# BackPage.net
KiCad netlist of a schematic drawn in Altium Designer
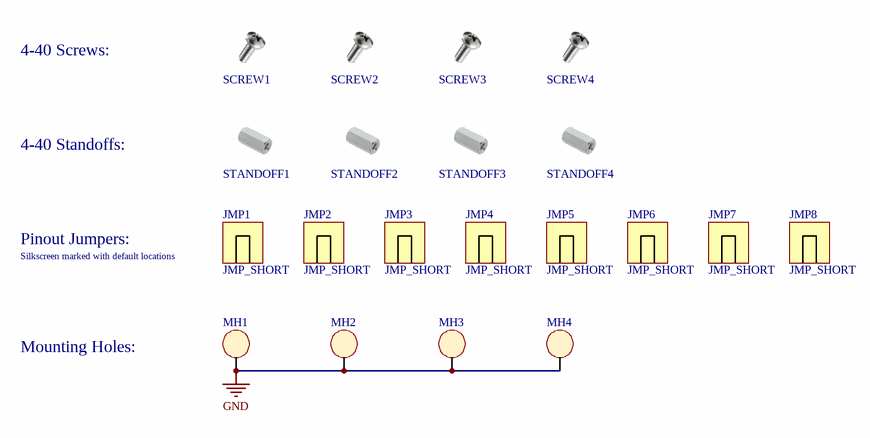
[diagram p0: BackPage.SchDoc]

(export (version "E")
  (design (tool "Eeschema 10.0.6"))
  (components
    (comp (ref "JMP1")
      (value "JMP_SHORT")
      (description "CONN JUMPER SHORTING .100\" GOLD")
      (libsource (lib "DAC") (part "JUMPER_SHORT"))
    )
    (comp (ref "JMP2")
      (value "JMP_SHORT")
      (description "CONN JUMPER SHORTING .100\" GOLD")
      (libsource (lib "DAC") (part "JUMPER_SHORT"))
    )
    (comp (ref "JMP3")
      (value "JMP_SHORT")
      (description "CONN JUMPER SHORTING .100\" GOLD")
      (libsource (lib "DAC") (part "JUMPER_SHORT"))
    )
    (comp (ref "JMP4")
      (value "JMP_SHORT")
      (description "CONN JUMPER SHORTING .100\" GOLD")
      (libsource (lib "DAC") (part "JUMPER_SHORT"))
    )
    (comp (ref "JMP5")
      (value "JMP_SHORT")
      (description "CONN JUMPER SHORTING .100\" GOLD")
      (libsource (lib "DAC") (part "JUMPER_SHORT"))
    )
    (comp (ref "JMP6")
      (value "JMP_SHORT")
      (description "CONN JUMPER SHORTING .100\" GOLD")
      (libsource (lib "DAC") (part "JUMPER_SHORT"))
    )
    (comp (ref "JMP7")
      (value "JMP_SHORT")
      (description "CONN JUMPER SHORTING .100\" GOLD")
      (libsource (lib "DAC") (part "JUMPER_SHORT"))
    )
    (comp (ref "JMP8")
      (value "JMP_SHORT")
      (description "CONN JUMPER SHORTING .100\" GOLD")
      (libsource (lib "DAC") (part "JUMPER_SHORT"))
    )
    (comp (ref "MH1")
      (value "MOUNT_HOLE")
      (footprint "MOUNTING_HOLE")
      (description "MOUNTING HOLE")
      (libsource (lib "DAC") (part "MOUNT_HOLE"))
    )
    (comp (ref "MH2")
      (value "MOUNT_HOLE")
      (footprint "MOUNTING_HOLE")
      (description "MOUNTING HOLE")
      (libsource (lib "DAC") (part "MOUNT_HOLE"))
    )
    (comp (ref "MH3")
      (value "MOUNT_HOLE")
      (footprint "MOUNTING_HOLE")
      (description "MOUNTING HOLE")
      (libsource (lib "DAC") (part "MOUNT_HOLE"))
    )
    (comp (ref "MH4")
      (value "MOUNT_HOLE")
      (footprint "MOUNTING_HOLE")
      (description "MOUNTING HOLE")
      (libsource (lib "DAC") (part "MOUNT_HOLE"))
    )
    (comp (ref "SCREW1")
      (value "9900")
      (description "#4-40 Pan Head Machine Screw Phillips Drive Stainless Steel")
      (libsource (lib "DAC") (part "SCREW 4-40"))
    )
    (comp (ref "SCREW2")
      (value "9900")
      (description "#4-40 Pan Head Machine Screw Phillips Drive Stainless Steel")
      (libsource (lib "DAC") (part "SCREW 4-40"))
    )
    (comp (ref "SCREW3")
      (value "9900")
      (description "#4-40 Pan Head Machine Screw Phillips Drive Stainless Steel")
      (libsource (lib "DAC") (part "SCREW 4-40"))
    )
    (comp (ref "SCREW4")
      (value "9900")
      (description "#4-40 Pan Head Machine Screw Phillips Drive Stainless Steel")
      (libsource (lib "DAC") (part "SCREW 4-40"))
    )
    (comp (ref "STANDOFF1")
      (value "2057-440-AL-7")
      (description "Hex Standoff Threaded #4-40 Aluminum 0.500\" (12.70mm) 1/2\"")
      (libsource (lib "DAC") (part "Standoff 4-40"))
    )
    (comp (ref "STANDOFF2")
      (value "2057-440-AL-7")
      (description "Hex Standoff Threaded #4-40 Aluminum 0.500\" (12.70mm) 1/2\"")
      (libsource (lib "DAC") (part "Standoff 4-40"))
    )
    (comp (ref "STANDOFF3")
      (value "2057-440-AL-7")
      (description "Hex Standoff Threaded #4-40 Aluminum 0.500\" (12.70mm) 1/2\"")
      (libsource (lib "DAC") (part "Standoff 4-40"))
    )
    (comp (ref "STANDOFF4")
      (value "2057-440-AL-7")
      (description "Hex Standoff Threaded #4-40 Aluminum 0.500\" (12.70mm) 1/2\"")
      (libsource (lib "DAC") (part "Standoff 4-40"))
    )
  )
  (nets
    (net (code "1") (name "GND") (class "Default")
      (node (ref "MH1") (pin "1") (pinfunction "1_1") (pintype "passive"))
      (node (ref "MH2") (pin "1") (pinfunction "1_1") (pintype "passive"))
      (node (ref "MH3") (pin "1") (pinfunction "1_1") (pintype "passive"))
      (node (ref "MH4") (pin "1") (pinfunction "1_1") (pintype "passive"))
    )
  )
)
